# ESP8266.net
KiCad netlist of a schematic drawn in Altium Designer
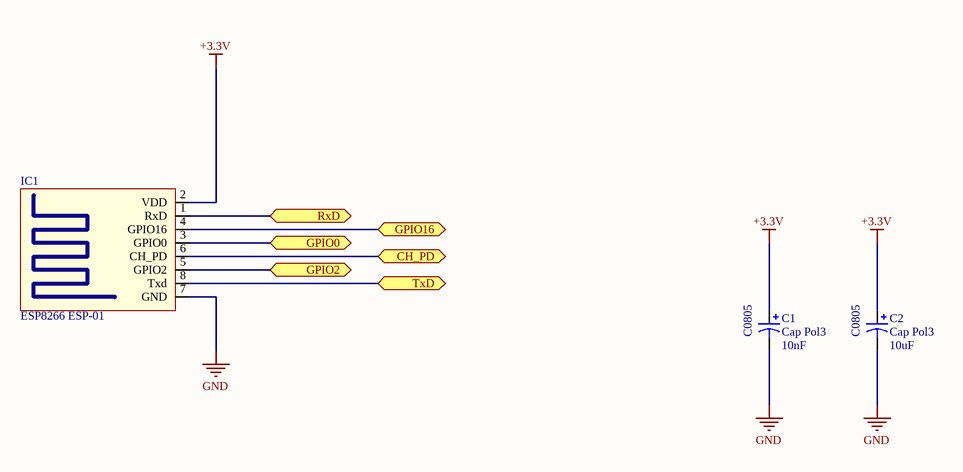
[diagram p0: ESP8266.SchDoc]

(export (version "E")
  (design (tool "Eeschema 10.0.6"))
  (components
    (comp (ref "C1")
      (value "Cap Pol3")
      (footprint "C0805")
      (description "Polarized Capacitor (Surface Mount)")
      (fields
        (field (name "PACKAGEREFERENCE") "C0805")
        (field (name "ALTIUM_VALUE") "10nF")
        (field (name "PUBLISHER") "Altium Limited")
      )
      (libsource (lib "Miscellaneous Devices") (part "Cap Pol3"))
    )
    (comp (ref "C2")
      (value "Cap Pol3")
      (footprint "C0805")
      (description "Polarized Capacitor (Surface Mount)")
      (fields
        (field (name "PACKAGEREFERENCE") "C0805")
        (field (name "ALTIUM_VALUE") "10uF")
        (field (name "PUBLISHER") "Altium Limited")
      )
      (libsource (lib "Miscellaneous Devices") (part "Cap Pol3"))
    )
    (comp (ref "IC1")
      (value "ESP8266 ESP-01")
      (footprint "ESP8266 ESP-01")
      (libsource (lib "ESP8266") (part "ESP8266 ESP-01"))
    )
  )
  (nets
    (net (code "1") (name "+3.3V") (class "Default")
      (node (ref "C1") (pin "1") (pinfunction "1_1") (pintype "passive"))
      (node (ref "C2") (pin "1") (pinfunction "1_1") (pintype "passive"))
      (node (ref "IC1") (pin "2") (pinfunction "VDD_2") (pintype "passive"))
    )
    (net (code "2") (name "/CH_PD") (class "Default")
      (node (ref "IC1") (pin "6") (pinfunction "CH_PD_6") (pintype "passive"))
    )
    (net (code "3") (name "/GPIO0") (class "Default")
      (node (ref "IC1") (pin "3") (pinfunction "GPIO0_3") (pintype "passive"))
    )
    (net (code "4") (name "/GPIO2") (class "Default")
      (node (ref "IC1") (pin "5") (pinfunction "GPIO2_5") (pintype "passive"))
    )
    (net (code "5") (name "/GPIO16") (class "Default")
      (node (ref "IC1") (pin "4") (pinfunction "GPIO16_4") (pintype "passive"))
    )
    (net (code "6") (name "/RxD") (class "Default")
      (node (ref "IC1") (pin "1") (pinfunction "RxD_1") (pintype "passive"))
    )
    (net (code "7") (name "/TxD") (class "Default")
      (node (ref "IC1") (pin "8") (pinfunction "Txd_8") (pintype "passive"))
    )
    (net (code "8") (name "GND") (class "Default")
      (node (ref "C1") (pin "2") (pinfunction "2_2") (pintype "passive"))
      (node (ref "C2") (pin "2") (pinfunction "2_2") (pintype "passive"))
      (node (ref "IC1") (pin "7") (pinfunction "GND_7") (pintype "passive"))
    )
  )
)
